# powerbrain.net
KiCad netlist of a schematic drawn in EAGLE
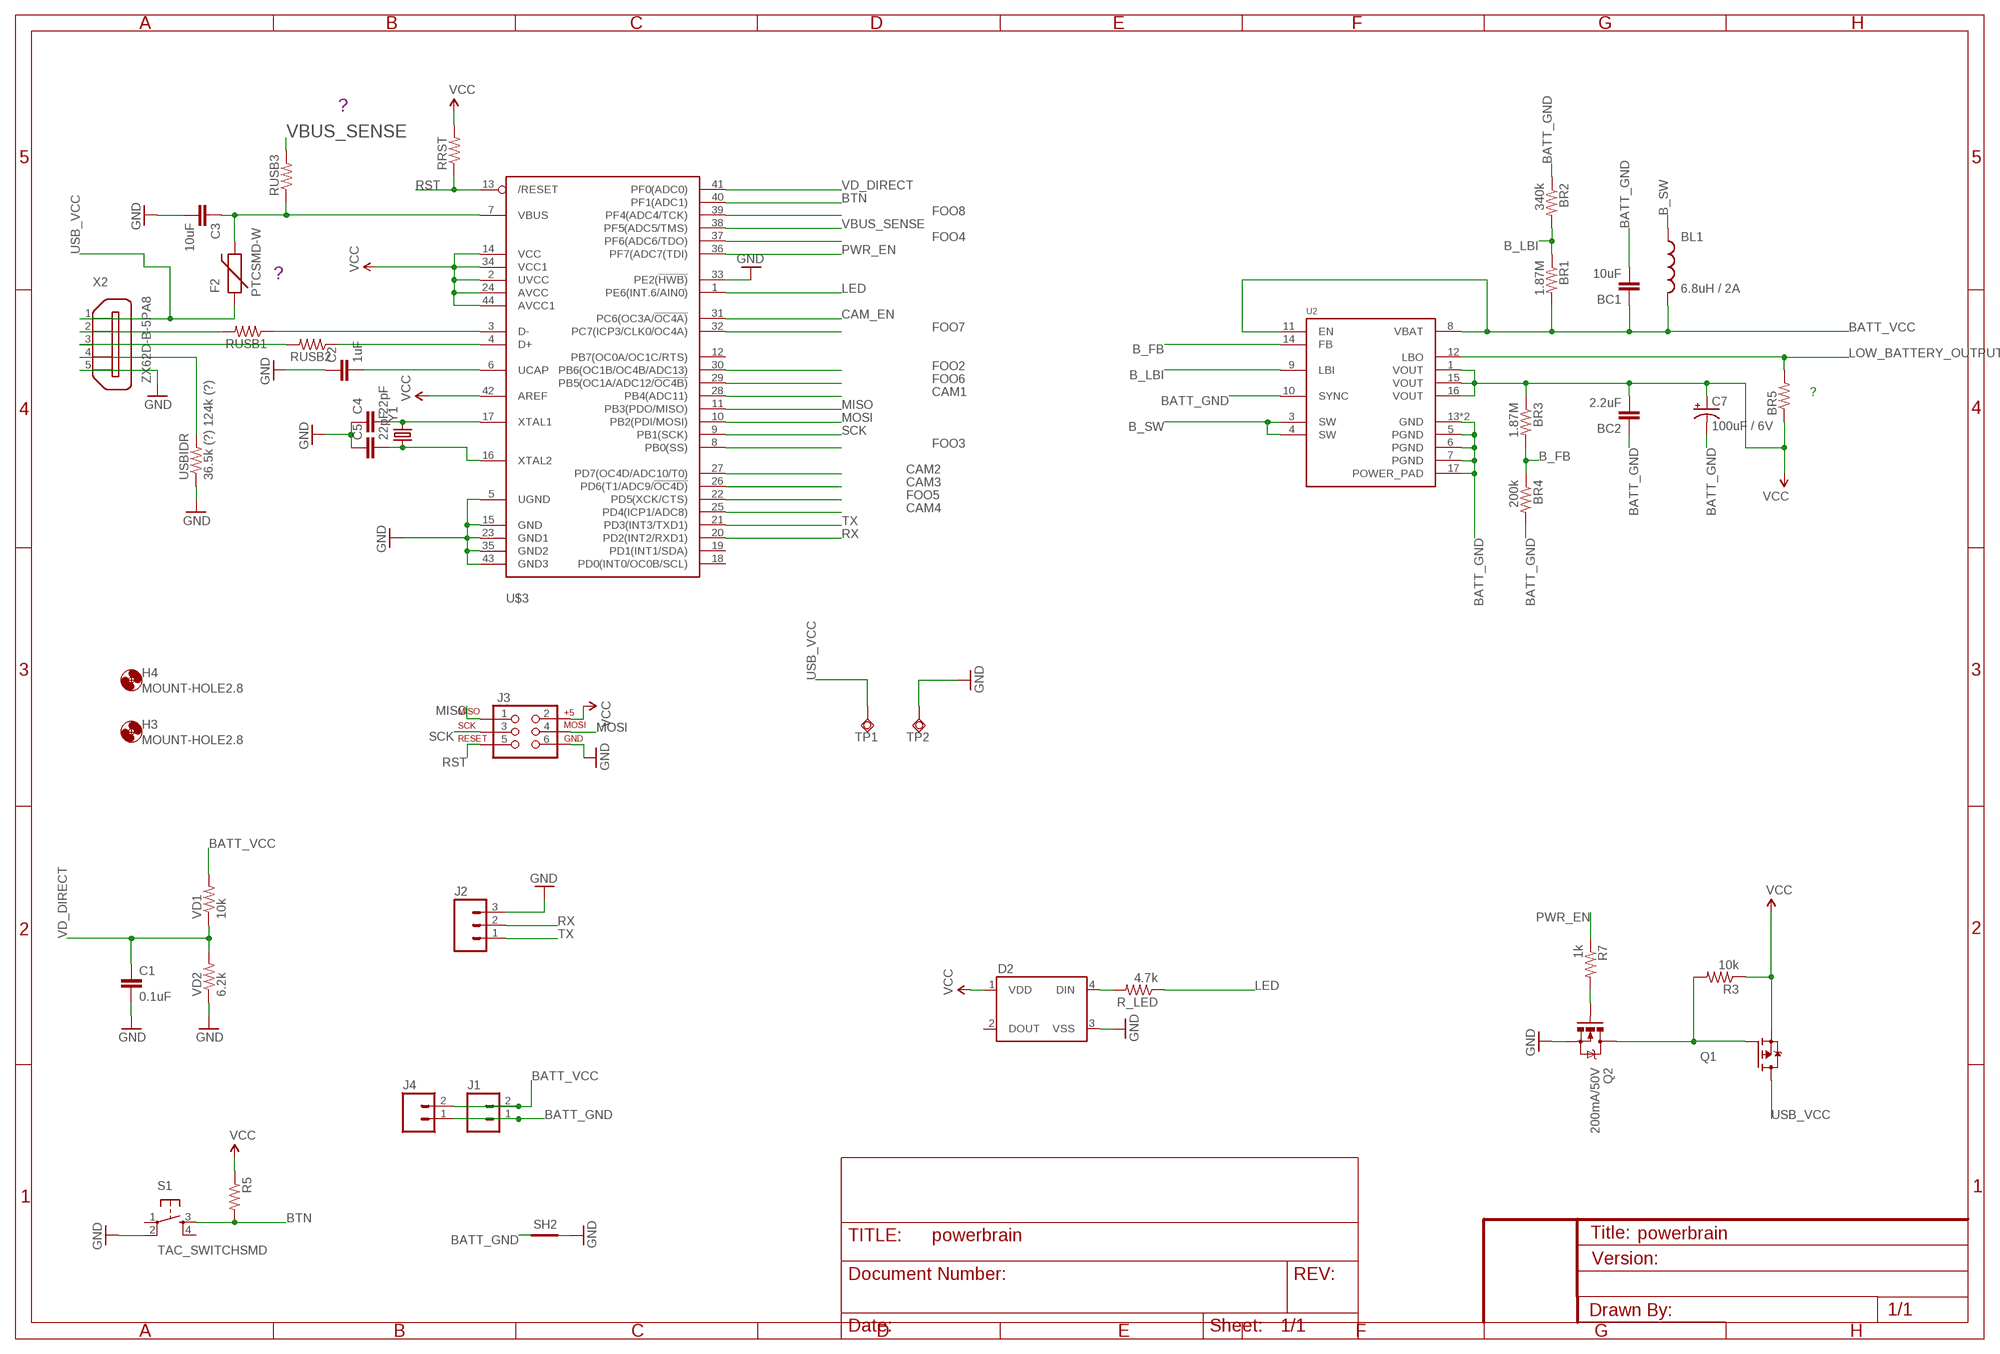
[diagram p0: schematic, sheet 1]

(export (version "E")
  (design (tool "Eeschema 10.0.6"))
  (components
    (comp (ref "BC1")
      (value "10uF")
      (footprint "eagle-import:1206")
      (libsource (lib "eagle-import") (part "CAP1206"))
    )
    (comp (ref "BC2")
      (value "2.2uF")
      (footprint "eagle-import:1206")
      (libsource (lib "eagle-import") (part "CAP1206"))
    )
    (comp (ref "BL1")
      (value "6.8uH / 2A")
      (footprint "eagle-import:SRU5028")
      (libsource (lib "eagle-import") (part "INDUCTORSRU5028"))
    )
    (comp (ref "BR1")
      (value "1.87M")
      (footprint "eagle-import:1206")
      (libsource (lib "eagle-import") (part "SparkFun-Resistors_RESISTOR1206"))
    )
    (comp (ref "BR2")
      (value "340k")
      (footprint "eagle-import:1206")
      (libsource (lib "eagle-import") (part "SparkFun-Resistors_RESISTOR1206"))
    )
    (comp (ref "BR3")
      (value "1.87M")
      (footprint "eagle-import:1206")
      (libsource (lib "eagle-import") (part "SparkFun-Resistors_RESISTOR1206"))
    )
    (comp (ref "BR4")
      (value "200k")
      (footprint "eagle-import:1206")
      (libsource (lib "eagle-import") (part "SparkFun-Resistors_RESISTOR1206"))
    )
    (comp (ref "BR5")
      (value "RESISTOR1206")
      (footprint "eagle-import:1206")
      (libsource (lib "eagle-import") (part "SparkFun-Resistors_RESISTOR1206"))
    )
    (comp (ref "C1")
      (value "0.1uF")
      (footprint "eagle-import:1206")
      (libsource (lib "eagle-import") (part "SparkFun-Passives_CAP1206"))
    )
    (comp (ref "C2")
      (value "1uF")
      (footprint "eagle-import:1206")
      (libsource (lib "eagle-import") (part "CAP1206"))
    )
    (comp (ref "C3")
      (value "10uF")
      (footprint "eagle-import:1206")
      (libsource (lib "eagle-import") (part "SparkFun-Passives_CAP1206"))
    )
    (comp (ref "C4")
      (value "22pF")
      (footprint "eagle-import:1206")
      (libsource (lib "eagle-import") (part "SparkFun-Passives_CAP1206"))
    )
    (comp (ref "C5")
      (value "22pF")
      (footprint "eagle-import:1206")
      (libsource (lib "eagle-import") (part "SparkFun-Passives_CAP1206"))
    )
    (comp (ref "C7")
      (value "100uF / 6V")
      (footprint "eagle-import:EIA3528-KIT")
      (libsource (lib "eagle-import") (part "CAP_POL3528-KIT"))
    )
    (comp (ref "D2")
      (value "WS2812B")
      (footprint "eagle-import:WS2812B")
      (libsource (lib "eagle-import") (part "WS2812B"))
    )
    (comp (ref "F2")
      (value "PTCSMD-W")
      (footprint "eagle-import:PTC-1206-WIDE")
      (libsource (lib "eagle-import") (part "PTCSMD-W"))
    )
    (comp (ref "H3")
      (value "MOUNT-HOLE2.8")
      (footprint "eagle-import:2,8")
      (libsource (lib "eagle-import") (part "MOUNT-HOLE2.8"))
    )
    (comp (ref "H4")
      (value "MOUNT-HOLE2.8")
      (footprint "eagle-import:2,8")
      (libsource (lib "eagle-import") (part "MOUNT-HOLE2.8"))
    )
    (comp (ref "J1")
      (value "M02LOCK")
      (footprint "eagle-import:1X02_LOCK")
      (libsource (lib "eagle-import") (part "M02LOCK"))
    )
    (comp (ref "J2")
      (value "M03PTH")
      (footprint "eagle-import:1X03")
      (libsource (lib "eagle-import") (part "M03PTH"))
    )
    (comp (ref "J3")
      (value "AVR_SPI_PRG_6PTH")
      (footprint "eagle-import:2X3")
      (libsource (lib "eagle-import") (part "AVR_SPI_PRG_6PTH"))
    )
    (comp (ref "J4")
      (value "M02LOCK")
      (footprint "eagle-import:1X02_LOCK")
      (libsource (lib "eagle-import") (part "M02LOCK"))
    )
    (comp (ref "Q1")
      (value "FDD4141TO252")
      (footprint "eagle-import:TO252")
      (libsource (lib "eagle-import") (part "FDD4141TO252"))
    )
    (comp (ref "Q2")
      (value "200mA/50V")
      (footprint "eagle-import:SOT23-3")
      (libsource (lib "eagle-import") (part "MOSFET-NCHANNELBSS138"))
    )
    (comp (ref "R3")
      (value "10k")
      (footprint "eagle-import:1206")
      (libsource (lib "eagle-import") (part "SparkFun-Resistors_RESISTOR1206"))
    )
    (comp (ref "R5")
      (value "RESISTOR1206")
      (footprint "eagle-import:1206")
      (libsource (lib "eagle-import") (part "RESISTOR1206"))
    )
    (comp (ref "R7")
      (value "1k")
      (footprint "eagle-import:1206")
      (libsource (lib "eagle-import") (part "SparkFun-Resistors_RESISTOR1206"))
    )
    (comp (ref "RRST")
      (value "RESISTOR1206")
      (footprint "eagle-import:1206")
      (libsource (lib "eagle-import") (part "RESISTOR1206"))
    )
    (comp (ref "RUSB1")
      (value "RESISTOR1206")
      (footprint "eagle-import:1206")
      (libsource (lib "eagle-import") (part "RESISTOR1206"))
    )
    (comp (ref "RUSB2")
      (value "RESISTOR1206")
      (footprint "eagle-import:1206")
      (libsource (lib "eagle-import") (part "RESISTOR1206"))
    )
    (comp (ref "RUSB3")
      (value "RESISTOR1206")
      (footprint "eagle-import:1206")
      (libsource (lib "eagle-import") (part "RESISTOR1206"))
    )
    (comp (ref "R_LED")
      (value "4.7k")
      (footprint "eagle-import:1206")
      (libsource (lib "eagle-import") (part "SparkFun-Resistors_RESISTOR1206"))
    )
    (comp (ref "S1")
      (value "TAC_SWITCHSMD")
      (footprint "eagle-import:TACTILE-PTH")
      (libsource (lib "eagle-import") (part "TAC_SWITCHPTH"))
    )
    (comp (ref "SH2")
      (value "SHORT-HT5")
      (footprint "eagle-import:SHORT_TOP-50")
      (libsource (lib "eagle-import") (part "SHORT-HT5"))
    )
    (comp (ref "TP1")
      (value "TPSQTP20R")
      (footprint "eagle-import:TP20R")
      (libsource (lib "eagle-import") (part "TPSQTP20R"))
    )
    (comp (ref "TP2")
      (value "TPSQTP20R")
      (footprint "eagle-import:TP20R")
      (libsource (lib "eagle-import") (part "TPSQTP20R"))
    )
    (comp (ref "U$3")
      (value "ATMEGA32U4-AU")
      (footprint "eagle-import:TQFP44")
      (libsource (lib "eagle-import") (part "ATMEGA32U4-AU"))
    )
    (comp (ref "U2")
      (value "TPS61090")
      (footprint "eagle-import:QFN65P400X400X100-17N")
      (fields (field (name "MF") "Texas Instruments"))
      (libsource (lib "eagle-import") (part "TPS61090"))
    )
    (comp (ref "USBIDR")
      (value "36.5k (?) 124k (?)")
      (footprint "eagle-import:1206")
      (libsource (lib "eagle-import") (part "RESISTOR1206"))
    )
    (comp (ref "VD1")
      (value "10k")
      (footprint "eagle-import:1206")
      (libsource (lib "eagle-import") (part "RESISTOR1206"))
    )
    (comp (ref "VD2")
      (value "6.2k")
      (footprint "eagle-import:1206")
      (libsource (lib "eagle-import") (part "RESISTOR1206"))
    )
    (comp (ref "X2")
      (value "ZX62D-B-5PA8")
      (footprint "eagle-import:ZX62D-B-5PA8")
      (fields (field (name "MF") "Hirose"))
      (libsource (lib "eagle-import") (part "ZX62D-B-5PA8"))
    )
    (comp (ref "Y1")
      (value "CRYSTALCRYSTAL-SMD-5X3-16MHZ")
      (footprint "eagle-import:CRYSTAL-SMD-5X3")
      (libsource (lib "eagle-import") (part "CRYSTALCRYSTAL-SMD-5X3-16MHZ"))
    )
  )
  (nets
    (net (code "1") (name "/BATT_GND") (class "Default")
      (node (ref "BC1") (pin "2") (pinfunction "2_2") (pintype "passive"))
      (node (ref "BC2") (pin "1") (pinfunction "1_1") (pintype "passive"))
      (node (ref "BR2") (pin "1") (pinfunction "1_1") (pintype "passive"))
      (node (ref "BR4") (pin "2") (pinfunction "2_2") (pintype "passive"))
      (node (ref "C7") (pin "C") (pinfunction "-_C") (pintype "passive"))
      (node (ref "J1") (pin "1") (pinfunction "1_1") (pintype "passive"))
      (node (ref "J4") (pin "1") (pinfunction "1_1") (pintype "passive"))
      (node (ref "SH2") (pin "1") (pinfunction "P$1_1") (pintype "bidirectional"))
      (node (ref "U2") (pin "10") (pinfunction "SYNC_10") (pintype "input"))
      (node (ref "U2") (pin "13") (pinfunction "GND_13") (pintype "power_in"))
      (node (ref "U2") (pin "17") (pinfunction "POWER_PAD_17") (pintype "power_in"))
      (node (ref "U2") (pin "5") (pinfunction "PGND_5") (pintype "power_in"))
      (node (ref "U2") (pin "6") (pinfunction "PGND_6") (pintype "power_in"))
      (node (ref "U2") (pin "7") (pinfunction "PGND_7") (pintype "power_in"))
      (node (ref "U2") (pin "P$1") (pinfunction "GND_P$1") (pintype "power_in"))
    )
    (net (code "2") (name "/BATT_VCC") (class "Default")
      (node (ref "BC1") (pin "1") (pinfunction "1_1") (pintype "passive"))
      (node (ref "BL1") (pin "2") (pinfunction "2_2") (pintype "passive"))
      (node (ref "BR1") (pin "2") (pinfunction "2_2") (pintype "passive"))
      (node (ref "J1") (pin "2") (pinfunction "2_2") (pintype "passive"))
      (node (ref "J4") (pin "2") (pinfunction "2_2") (pintype "passive"))
      (node (ref "U2") (pin "11") (pinfunction "EN_11") (pintype "input"))
      (node (ref "U2") (pin "8") (pinfunction "VBAT_8") (pintype "power_in"))
      (node (ref "VD1") (pin "2") (pinfunction "2_2") (pintype "passive"))
    )
    (net (code "3") (name "/BTN") (class "Default")
      (node (ref "R5") (pin "2") (pinfunction "2_2") (pintype "passive"))
      (node (ref "S1") (pin "3") (pinfunction "3_3") (pintype "passive"))
      (node (ref "U$3") (pin "40") (pinfunction "PF1(ADC1)_40") (pintype "bidirectional"))
    )
    (net (code "4") (name "/B_FB") (class "Default")
      (node (ref "BR3") (pin "2") (pinfunction "2_2") (pintype "passive"))
      (node (ref "BR4") (pin "1") (pinfunction "1_1") (pintype "passive"))
      (node (ref "U2") (pin "14") (pinfunction "FB_14") (pintype "input"))
    )
    (net (code "5") (name "/B_LBI") (class "Default")
      (node (ref "BR1") (pin "1") (pinfunction "1_1") (pintype "passive"))
      (node (ref "BR2") (pin "2") (pinfunction "2_2") (pintype "passive"))
      (node (ref "U2") (pin "9") (pinfunction "LBI_9") (pintype "input"))
    )
    (net (code "6") (name "/B_SW") (class "Default")
      (node (ref "BL1") (pin "1") (pinfunction "1_1") (pintype "passive"))
      (node (ref "U2") (pin "3") (pinfunction "SW_3") (pintype "input"))
      (node (ref "U2") (pin "4") (pinfunction "SW_4") (pintype "input"))
    )
    (net (code "7") (name "/CAM1") (class "Default")
      (node (ref "U$3") (pin "28") (pinfunction "PB4(ADC11)_28") (pintype "bidirectional"))
    )
    (net (code "8") (name "/CAM2") (class "Default")
      (node (ref "U$3") (pin "27") (pinfunction "PD7(OC4D/ADC10/T0)_27") (pintype "bidirectional"))
    )
    (net (code "9") (name "/CAM3") (class "Default")
      (node (ref "U$3") (pin "26") (pinfunction "PD6(T1/ADC9/~{OC4D})_26") (pintype "bidirectional"))
    )
    (net (code "10") (name "/CAM4") (class "Default")
      (node (ref "U$3") (pin "25") (pinfunction "PD4(ICP1/ADC8)_25") (pintype "bidirectional"))
    )
    (net (code "11") (name "/CAM_EN") (class "Default")
      (node (ref "U$3") (pin "31") (pinfunction "PC6(OC3A/~{OC4A})_31") (pintype "bidirectional"))
    )
    (net (code "12") (name "/FOO2") (class "Default")
      (node (ref "U$3") (pin "30") (pinfunction "PB6(OC1B/OC4B/ADC13)_30") (pintype "bidirectional"))
    )
    (net (code "13") (name "/FOO3") (class "Default")
      (node (ref "U$3") (pin "8") (pinfunction "PB0(SS)_8") (pintype "bidirectional"))
    )
    (net (code "14") (name "/FOO4") (class "Default")
      (node (ref "U$3") (pin "37") (pinfunction "PF6(ADC6/TDO)_37") (pintype "bidirectional"))
    )
    (net (code "15") (name "/FOO5") (class "Default")
      (node (ref "U$3") (pin "22") (pinfunction "PD5(XCK/CTS)_22") (pintype "bidirectional"))
    )
    (net (code "16") (name "/FOO6") (class "Default")
      (node (ref "U$3") (pin "29") (pinfunction "PB5(OC1A/ADC12/~{OC4B})_29") (pintype "bidirectional"))
    )
    (net (code "17") (name "/FOO7") (class "Default")
      (node (ref "U$3") (pin "32") (pinfunction "PC7(ICP3/CLK0/OC4A)_32") (pintype "bidirectional"))
    )
    (net (code "18") (name "/FOO8") (class "Default")
      (node (ref "U$3") (pin "39") (pinfunction "PF4(ADC4/TCK)_39") (pintype "bidirectional"))
    )
    (net (code "19") (name "/LED") (class "Default")
      (node (ref "R_LED") (pin "1") (pinfunction "1_1") (pintype "passive"))
      (node (ref "U$3") (pin "1") (pinfunction "PE6(INT.6/AIN0)_1") (pintype "bidirectional"))
    )
    (net (code "20") (name "/LOW_BATTERY_OUTPUT") (class "Default")
      (node (ref "BR5") (pin "2") (pinfunction "2_2") (pintype "passive"))
      (node (ref "U2") (pin "12") (pinfunction "LBO_12") (pintype "output"))
    )
    (net (code "21") (name "/MISO") (class "Default")
      (node (ref "J3") (pin "1") (pinfunction "1_1") (pintype "passive"))
      (node (ref "U$3") (pin "11") (pinfunction "PB3(PDO/MISO)_11") (pintype "bidirectional"))
    )
    (net (code "22") (name "/MOSI") (class "Default")
      (node (ref "J3") (pin "4") (pinfunction "4_4") (pintype "passive"))
      (node (ref "U$3") (pin "10") (pinfunction "PB2(PDI/MOSI)_10") (pintype "bidirectional"))
    )
    (net (code "23") (name "/PWR_EN") (class "Default")
      (node (ref "R7") (pin "1") (pinfunction "1_1") (pintype "passive"))
      (node (ref "U$3") (pin "36") (pinfunction "PF7(ADC7(TDI)_36") (pintype "bidirectional"))
    )
    (net (code "24") (name "/RST") (class "Default")
      (node (ref "J3") (pin "5") (pinfunction "5_5") (pintype "passive"))
      (node (ref "RRST") (pin "1") (pinfunction "1_1") (pintype "passive"))
      (node (ref "U$3") (pin "13") (pinfunction "/RESET_13") (pintype "bidirectional"))
    )
    (net (code "25") (name "/RX") (class "Default")
      (node (ref "J2") (pin "2") (pinfunction "2_2") (pintype "passive"))
      (node (ref "U$3") (pin "20") (pinfunction "PD2(INT2/RXD1)_20") (pintype "bidirectional"))
    )
    (net (code "26") (name "/SCK") (class "Default")
      (node (ref "J3") (pin "3") (pinfunction "3_3") (pintype "passive"))
      (node (ref "U$3") (pin "9") (pinfunction "PB1(SCK)_9") (pintype "bidirectional"))
    )
    (net (code "27") (name "/TX") (class "Default")
      (node (ref "J2") (pin "1") (pinfunction "1_1") (pintype "passive"))
      (node (ref "U$3") (pin "21") (pinfunction "PD3(INT3/TXD1)_21") (pintype "bidirectional"))
    )
    (net (code "28") (name "/USB_VCC") (class "Default")
      (node (ref "F2") (pin "1") (pinfunction "1_1") (pintype "bidirectional"))
      (node (ref "Q1") (pin "3") (pinfunction "D_3") (pintype "passive"))
      (node (ref "TP1") (pin "TP") (pinfunction "TP_TP") (pintype "input"))
      (node (ref "X2") (pin "1") (pinfunction "1_1") (pintype "passive"))
    )
    (net (code "29") (name "/VBUS_SENSE") (class "Default")
      (node (ref "RUSB3") (pin "2") (pinfunction "2_2") (pintype "passive"))
      (node (ref "U$3") (pin "38") (pinfunction "PF5(ADC5/TMS)_38") (pintype "bidirectional"))
    )
    (net (code "30") (name "/VD_DIRECT") (class "Default")
      (node (ref "C1") (pin "1") (pinfunction "1_1") (pintype "passive"))
      (node (ref "U$3") (pin "41") (pinfunction "PF0(ADC0)_41") (pintype "bidirectional"))
      (node (ref "VD1") (pin "1") (pinfunction "1_1") (pintype "passive"))
      (node (ref "VD2") (pin "2") (pinfunction "2_2") (pintype "passive"))
    )
    (net (code "31") (name "GND") (class "Default")
      (node (ref "C1") (pin "2") (pinfunction "2_2") (pintype "passive"))
      (node (ref "C2") (pin "1") (pinfunction "1_1") (pintype "passive"))
      (node (ref "C3") (pin "2") (pinfunction "2_2") (pintype "passive"))
      (node (ref "C4") (pin "1") (pinfunction "1_1") (pintype "passive"))
      (node (ref "C5") (pin "1") (pinfunction "1_1") (pintype "passive"))
      (node (ref "D2") (pin "3") (pinfunction "VSS_3") (pintype "power_in"))
      (node (ref "J2") (pin "3") (pinfunction "3_3") (pintype "passive"))
      (node (ref "J3") (pin "6") (pinfunction "6_6") (pintype "passive"))
      (node (ref "Q2") (pin "2") (pinfunction "S_2") (pintype "passive"))
      (node (ref "S1") (pin "2") (pinfunction "2_2") (pintype "passive"))
      (node (ref "SH2") (pin "2") (pinfunction "P$2_2") (pintype "bidirectional"))
      (node (ref "TP2") (pin "TP") (pinfunction "TP_TP") (pintype "input"))
      (node (ref "U$3") (pin "15") (pinfunction "GND_15") (pintype "bidirectional"))
      (node (ref "U$3") (pin "23") (pinfunction "GND1_23") (pintype "bidirectional"))
      (node (ref "U$3") (pin "33") (pinfunction "PE2(~{HWB})_33") (pintype "bidirectional"))
      (node (ref "U$3") (pin "35") (pinfunction "GND2_35") (pintype "bidirectional"))
      (node (ref "U$3") (pin "43") (pinfunction "GND3_43") (pintype "bidirectional"))
      (node (ref "U$3") (pin "5") (pinfunction "UGND_5") (pintype "bidirectional"))
      (node (ref "USBIDR") (pin "1") (pinfunction "1_1") (pintype "passive"))
      (node (ref "VD2") (pin "1") (pinfunction "1_1") (pintype "passive"))
      (node (ref "X2") (pin "5") (pinfunction "5_5") (pintype "passive"))
    )
    (net (code "32") (name "Net-(D2-DIN)") (class "Default")
      (node (ref "D2") (pin "4") (pinfunction "DIN_4") (pintype "input"))
      (node (ref "R_LED") (pin "2") (pinfunction "2_2") (pintype "passive"))
    )
    (net (code "33") (name "Net-(Q1-G)") (class "Default")
      (node (ref "Q1") (pin "1") (pinfunction "G_1") (pintype "passive"))
      (node (ref "Q2") (pin "3") (pinfunction "D_3") (pintype "passive"))
      (node (ref "R3") (pin "2") (pinfunction "2_2") (pintype "passive"))
    )
    (net (code "34") (name "Net-(Q2-G)") (class "Default")
      (node (ref "Q2") (pin "1") (pinfunction "G_1") (pintype "passive"))
      (node (ref "R7") (pin "2") (pinfunction "2_2") (pintype "passive"))
    )
    (net (code "35") (name "Net-(RUSB1-Pad2)") (class "Default")
      (node (ref "RUSB1") (pin "2") (pinfunction "2_2") (pintype "passive"))
      (node (ref "X2") (pin "2") (pinfunction "2_2") (pintype "passive"))
    )
    (net (code "36") (name "Net-(RUSB2-Pad2)") (class "Default")
      (node (ref "RUSB2") (pin "2") (pinfunction "2_2") (pintype "passive"))
      (node (ref "X2") (pin "3") (pinfunction "3_3") (pintype "passive"))
    )
    (net (code "37") (name "Net-(U$3-D+)") (class "Default")
      (node (ref "RUSB2") (pin "1") (pinfunction "1_1") (pintype "passive"))
      (node (ref "U$3") (pin "4") (pinfunction "D+_4") (pintype "bidirectional"))
    )
    (net (code "38") (name "Net-(U$3-D-)") (class "Default")
      (node (ref "RUSB1") (pin "1") (pinfunction "1_1") (pintype "passive"))
      (node (ref "U$3") (pin "3") (pinfunction "D-_3") (pintype "bidirectional"))
    )
    (net (code "39") (name "Net-(U$3-UCAP)") (class "Default")
      (node (ref "C2") (pin "2") (pinfunction "2_2") (pintype "passive"))
      (node (ref "U$3") (pin "6") (pinfunction "UCAP_6") (pintype "bidirectional"))
    )
    (net (code "40") (name "Net-(U$3-VBUS)") (class "Default")
      (node (ref "C3") (pin "1") (pinfunction "1_1") (pintype "passive"))
      (node (ref "F2") (pin "2") (pinfunction "2_2") (pintype "bidirectional"))
      (node (ref "RUSB3") (pin "1") (pinfunction "1_1") (pintype "passive"))
      (node (ref "U$3") (pin "7") (pinfunction "VBUS_7") (pintype "bidirectional"))
    )
    (net (code "41") (name "Net-(U$3-XTAL1)") (class "Default")
      (node (ref "C4") (pin "2") (pinfunction "2_2") (pintype "passive"))
      (node (ref "U$3") (pin "17") (pinfunction "XTAL1_17") (pintype "bidirectional"))
      (node (ref "Y1") (pin "3") (pinfunction "2_3") (pintype "passive"))
    )
    (net (code "42") (name "Net-(U$3-XTAL2)") (class "Default")
      (node (ref "C5") (pin "2") (pinfunction "2_2") (pintype "passive"))
      (node (ref "U$3") (pin "16") (pinfunction "XTAL2_16") (pintype "bidirectional"))
      (node (ref "Y1") (pin "1") (pinfunction "1_1") (pintype "passive"))
    )
    (net (code "43") (name "Net-(USBIDR-Pad2)") (class "Default")
      (node (ref "USBIDR") (pin "2") (pinfunction "2_2") (pintype "passive"))
      (node (ref "X2") (pin "4") (pinfunction "4_4") (pintype "passive"))
    )
    (net (code "44") (name "VCC") (class "Default")
      (node (ref "BC2") (pin "2") (pinfunction "2_2") (pintype "passive"))
      (node (ref "BR3") (pin "1") (pinfunction "1_1") (pintype "passive"))
      (node (ref "BR5") (pin "1") (pinfunction "1_1") (pintype "passive"))
      (node (ref "C7") (pin "A") (pinfunction "+_A") (pintype "passive"))
      (node (ref "D2") (pin "1") (pinfunction "VDD_1") (pintype "power_in"))
      (node (ref "J3") (pin "2") (pinfunction "2_2") (pintype "passive"))
      (node (ref "Q1") (pin "2") (pinfunction "S_2") (pintype "passive"))
      (node (ref "R3") (pin "1") (pinfunction "1_1") (pintype "passive"))
      (node (ref "R5") (pin "1") (pinfunction "1_1") (pintype "passive"))
      (node (ref "RRST") (pin "2") (pinfunction "2_2") (pintype "passive"))
      (node (ref "U$3") (pin "14") (pinfunction "VCC_14") (pintype "bidirectional"))
      (node (ref "U$3") (pin "2") (pinfunction "UVCC_2") (pintype "bidirectional"))
      (node (ref "U$3") (pin "24") (pinfunction "AVCC_24") (pintype "bidirectional"))
      (node (ref "U$3") (pin "34") (pinfunction "VCC1_34") (pintype "bidirectional"))
      (node (ref "U$3") (pin "42") (pinfunction "AREF_42") (pintype "bidirectional"))
      (node (ref "U$3") (pin "44") (pinfunction "AVCC1_44") (pintype "bidirectional"))
      (node (ref "U2") (pin "1") (pinfunction "VOUT_1") (pintype "output"))
      (node (ref "U2") (pin "15") (pinfunction "VOUT_15") (pintype "output"))
      (node (ref "U2") (pin "16") (pinfunction "VOUT_16") (pintype "output"))
    )
    (net (code "45") (name "unconnected-(D2-DOUT-Pad2)") (class "Default")
      (node (ref "D2") (pin "2") (pinfunction "DOUT_2") (pintype "output"))
    )
    (net (code "46") (name "unconnected-(S1-Pad1)") (class "Default")
      (node (ref "S1") (pin "1") (pinfunction "1_1") (pintype "passive"))
    )
    (net (code "47") (name "unconnected-(S1-Pad4)") (class "Default")
      (node (ref "S1") (pin "4") (pinfunction "4_4") (pintype "passive"))
    )
    (net (code "48") (name "unconnected-(U$3-PB7(OC0A{slash}OC1C{slash}RTS)-Pad12)") (class "Default")
      (node (ref "U$3") (pin "12") (pinfunction "PB7(OC0A/OC1C/RTS)_12") (pintype "bidirectional"))
    )
    (net (code "49") (name "unconnected-(U$3-PD0(INT0{slash}OC0B{slash}SCL)-Pad18)") (class "Default")
      (node (ref "U$3") (pin "18") (pinfunction "PD0(INT0/OC0B/SCL)_18") (pintype "bidirectional"))
    )
    (net (code "50") (name "unconnected-(U$3-PD1(INT1{slash}SDA)-Pad19)") (class "Default")
      (node (ref "U$3") (pin "19") (pinfunction "PD1(INT1/SDA)_19") (pintype "bidirectional"))
    )
  )
)
